# NanoV3_2.net
KiCad netlist of a schematic drawn in EAGLE
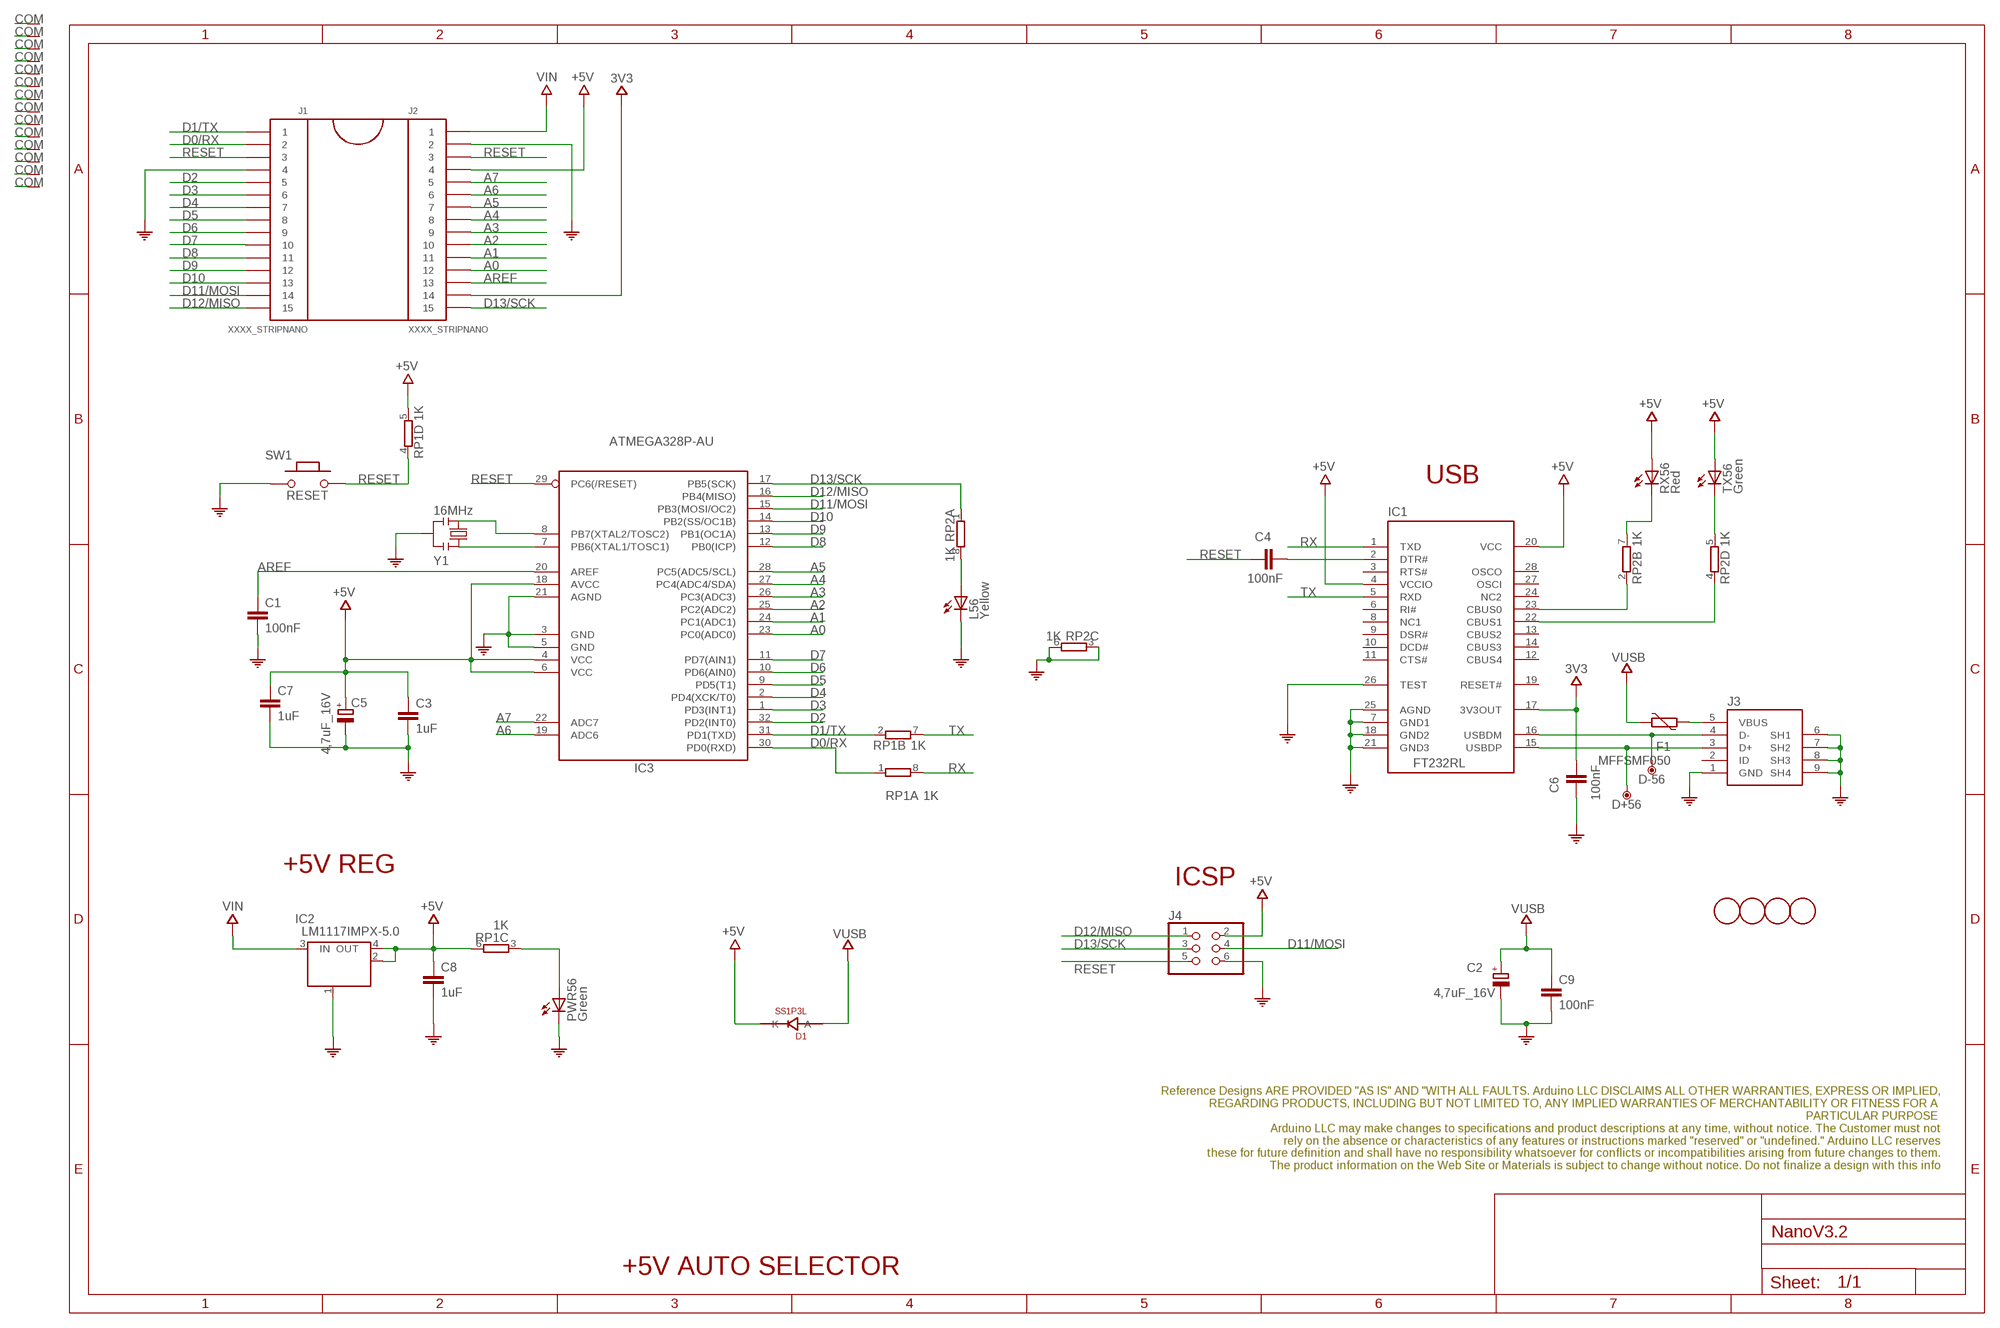
[diagram p0: schematic, sheet 1]

(export (version "E")
  (design (tool "Eeschema 10.0.6"))
  (components
    (comp (ref "C1")
      (value "100nF")
      (footprint "eagle-import:C0603-ROUND")
      (fields (field (name "PART_NUMBER") "cl10b104kbnc"))
      (libsource (lib "eagle-import") (part "0015_100NF_0603"))
    )
    (comp (ref "C2")
      (value "4,7uF_16V")
      (footprint "eagle-import:TAN-A")
      (fields (field (name "PART_NUMBER") "TAJA475MO16RNJ"))
      (libsource (lib "eagle-import") (part "0833_TAJA475MO16RNJ"))
    )
    (comp (ref "C3")
      (value "1uF")
      (footprint "eagle-import:C0603-ROUND")
      (fields (field (name "PART_NUMBER") "1uF_0603/GRM188R61E105KA12D"))
      (libsource (lib "eagle-import") (part "0006_1UF_0603/GRM188R61E105KA12D"))
    )
    (comp (ref "C4")
      (value "100nF")
      (footprint "eagle-import:C0603-ROUND")
      (fields (field (name "PART_NUMBER") "cl10b104kbnc"))
      (libsource (lib "eagle-import") (part "0015_100NF_0603"))
    )
    (comp (ref "C5")
      (value "4,7uF_16V")
      (footprint "eagle-import:TAN-A")
      (fields (field (name "PART_NUMBER") "TAJA475MO16RNJ"))
      (libsource (lib "eagle-import") (part "0833_TAJA475MO16RNJ"))
    )
    (comp (ref "C6")
      (value "100nF")
      (footprint "eagle-import:C0603-ROUND")
      (fields (field (name "PART_NUMBER") "cl10b104kbnc"))
      (libsource (lib "eagle-import") (part "0015_100NF_0603"))
    )
    (comp (ref "C7")
      (value "1uF")
      (footprint "eagle-import:C0603-ROUND")
      (fields (field (name "PART_NUMBER") "1uF_0603/GRM188R61E105KA12D"))
      (libsource (lib "eagle-import") (part "0006_1UF_0603/GRM188R61E105KA12D"))
    )
    (comp (ref "C8")
      (value "1uF")
      (footprint "eagle-import:C0603-ROUND")
      (fields (field (name "PART_NUMBER") "1uF_0603/GRM188R61E105KA12D"))
      (libsource (lib "eagle-import") (part "0006_1UF_0603/GRM188R61E105KA12D"))
    )
    (comp (ref "C9")
      (value "100nF")
      (footprint "eagle-import:C0603-ROUND")
      (fields (field (name "PART_NUMBER") "cl10b104kbnc"))
      (libsource (lib "eagle-import") (part "0015_100NF_0603"))
    )
    (comp (ref "D+56")
      (value "DNP")
      (footprint "eagle-import:TP-1.00MM")
      (libsource (lib "eagle-import") (part "TPTP-1.00MM"))
    )
    (comp (ref "D-56")
      (value "DNP")
      (footprint "eagle-import:TP-1.00MM")
      (libsource (lib "eagle-import") (part "TPTP-1.00MM"))
    )
    (comp (ref "D1")
      (value "SS1P3L")
      (footprint "eagle-import:DO220AAL")
      (fields (field (name "PART_NUMBER") "SS1P3L-M3/84A"))
      (libsource (lib "eagle-import") (part "0025_SS1P3L-M3/84A"))
    )
    (comp (ref "F1")
      (value "MFFSMF050")
      (footprint "eagle-import:0603-1608X90N")
      (fields (field (name "MANUFACTURER") "Bourns Inc "))
      (libsource (lib "eagle-import") (part "PTC"))
    )
    (comp (ref "FRAME1")
      (value "DNP")
      (footprint "eagle-import:FRAME")
      (libsource (lib "eagle-import") (part "A3-FRAME-STANDARD"))
    )
    (comp (ref "IC1")
      (value "FT232RL")
      (footprint "eagle-import:SSOP28")
      (libsource (lib "eagle-import") (part "0226_FT232RL"))
    )
    (comp (ref "IC2")
      (value "LM1117IMPX-5.0")
      (footprint "eagle-import:LINEAR_SOT223")
      (libsource (lib "eagle-import") (part "0022_LM1117IMPX-5.0"))
    )
    (comp (ref "IC3")
      (value "ATMEGA328P-AU")
      (footprint "eagle-import:TQFP32-08")
      (libsource (lib "eagle-import") (part "0265_ATMEGA328P-AU"))
    )
    (comp (ref "J1")
      (value "XXXX_STRIPNANO")
      (footprint "eagle-import:HEAD15-NOSS")
      (libsource (lib "eagle-import") (part "XXXX_STRIPNANO"))
    )
    (comp (ref "J2")
      (value "XXXX_STRIPNANO")
      (footprint "eagle-import:HEAD15-NOSS")
      (libsource (lib "eagle-import") (part "XXXX_STRIPNANO"))
    )
    (comp (ref "J3")
      (value "0219_14850")
      (footprint "eagle-import:USB-MINI-B_2")
      (fields (field (name "PART_NUMBER") "14850"))
      (libsource (lib "eagle-import") (part "0219_14850"))
    )
    (comp (ref "J4")
      (value "0114_PH254-203DF118A00V")
      (footprint "eagle-import:2X03")
      (fields (field (name "PART_NUMBER") "PH254-203DF118A00V"))
      (libsource (lib "eagle-import") (part "0114_PH254-203DF118A00V"))
    )
    (comp (ref "L56")
      (value "Yellow")
      (footprint "eagle-import:CHIPLED_0805")
      (fields (field (name "PART_NUMBER") "KPT-2012YC"))
      (libsource (lib "eagle-import") (part "0044_KPT-2012YC"))
    )
    (comp (ref "PWR56")
      (value "Green")
      (footprint "eagle-import:CHIPLED_0805")
      (fields (field (name "PART_NUMBER") "KPT-2012SGC"))
      (libsource (lib "eagle-import") (part "0043_KPT-2012SGC"))
    )
    (comp (ref "RP1")
      (value "1K")
      (footprint "eagle-import:CAY16")
      (fields (field (name "PART_NUMBER") "064R_1K_/_CAY16-102J4LF"))
      (libsource (lib "eagle-import") (part "0005_064R_1K_/_CAY16-102J4LF"))
    )
    (comp (ref "RP2")
      (value "1K")
      (footprint "eagle-import:CAY16")
      (fields (field (name "PART_NUMBER") "064R_1K_/_CAY16-102J4LF"))
      (libsource (lib "eagle-import") (part "0005_064R_1K_/_CAY16-102J4LF"))
    )
    (comp (ref "RX56")
      (value "Red")
      (footprint "eagle-import:CHIPLED_0805")
      (fields (field (name "PART_NUMBER") "KTP-2012SURCK"))
      (libsource (lib "eagle-import") (part "0181_KTP-2012SURCK"))
    )
    (comp (ref "SW1")
      (value "RESET")
      (footprint "eagle-import:SMD_157SW")
      (fields (field (name "PART_NUMBER") "IT-1185AP1C-160G-G_T&R"))
      (libsource (lib "eagle-import") (part "0173_IT-1185AP1C-160G-G_T&R"))
    )
    (comp (ref "TX56")
      (value "Green")
      (footprint "eagle-import:CHIPLED_0805")
      (fields (field (name "PART_NUMBER") "KPT-2012SGC"))
      (libsource (lib "eagle-import") (part "0043_KPT-2012SGC"))
    )
    (comp (ref "U$4")
      (value "DNP")
      (footprint "eagle-import:FD-1-1.5")
      (libsource (lib "eagle-import") (part "FIDUCIAL-1.5MM"))
    )
    (comp (ref "U$5")
      (value "DNP")
      (footprint "eagle-import:FD-1-1.5")
      (libsource (lib "eagle-import") (part "FIDUCIAL-1.5MM"))
    )
    (comp (ref "U$53")
      (value "DNP")
      (footprint "eagle-import:FD-1-1.5")
      (libsource (lib "eagle-import") (part "FIDUCIAL-1.5MM"))
    )
    (comp (ref "U$54")
      (value "DNP")
      (footprint "eagle-import:FD-1-1.5")
      (libsource (lib "eagle-import") (part "FIDUCIAL-1.5MM"))
    )
    (comp (ref "VP_0")
      (value "VPDEV0")
      (footprint "eagle-import:VPAC0")
      (libsource (lib "eagle-import") (part "VPDEV0"))
    )
    (comp (ref "VP_1")
      (value "VPDEV0")
      (footprint "eagle-import:VPAC0")
      (libsource (lib "eagle-import") (part "VPDEV0"))
    )
    (comp (ref "VP_2")
      (value "VPDEV0")
      (footprint "eagle-import:VPAC0")
      (libsource (lib "eagle-import") (part "VPDEV0"))
    )
    (comp (ref "VP_3")
      (value "VPDEV0")
      (footprint "eagle-import:VPAC0")
      (libsource (lib "eagle-import") (part "VPDEV0"))
    )
    (comp (ref "VP_4")
      (value "VPDEV0")
      (footprint "eagle-import:VPAC0")
      (libsource (lib "eagle-import") (part "VPDEV0"))
    )
    (comp (ref "VP_5")
      (value "VPDEV0")
      (footprint "eagle-import:VPAC0")
      (libsource (lib "eagle-import") (part "VPDEV0"))
    )
    (comp (ref "VP_6")
      (value "VPDEV0")
      (footprint "eagle-import:VPAC0")
      (libsource (lib "eagle-import") (part "VPDEV0"))
    )
    (comp (ref "VP_7")
      (value "VPDEV0")
      (footprint "eagle-import:VPAC0")
      (libsource (lib "eagle-import") (part "VPDEV0"))
    )
    (comp (ref "VP_8")
      (value "VPDEV0")
      (footprint "eagle-import:VPAC0")
      (libsource (lib "eagle-import") (part "VPDEV0"))
    )
    (comp (ref "VP_9")
      (value "VPDEV0")
      (footprint "eagle-import:VPAC0")
      (libsource (lib "eagle-import") (part "VPDEV0"))
    )
    (comp (ref "VP_10")
      (value "VPDEV0")
      (footprint "eagle-import:VPAC0")
      (libsource (lib "eagle-import") (part "VPDEV0"))
    )
    (comp (ref "VP_11")
      (value "VPDEV0")
      (footprint "eagle-import:VPAC0")
      (libsource (lib "eagle-import") (part "VPDEV0"))
    )
    (comp (ref "VP_12")
      (value "VPDEV0")
      (footprint "eagle-import:VPAC0")
      (libsource (lib "eagle-import") (part "VPDEV0"))
    )
    (comp (ref "VP_13")
      (value "VPDEV0")
      (footprint "eagle-import:VPAC0")
      (libsource (lib "eagle-import") (part "VPDEV0"))
    )
    (comp (ref "Y1")
      (value "16MHz")
      (footprint "eagle-import:RESONATOR")
      (fields (field (name "PART_NUMBER") "CSTCE16M0V53-R0"))
      (libsource (lib "eagle-import") (part "0011_CSTCE16M0V53-R0"))
    )
  )
  (nets
    (net (code "1") (name "+5V") (class "Default")
      (node (ref "C3") (pin "1") (pinfunction "1_1") (pintype "passive"))
      (node (ref "C5") (pin "1") (pinfunction "+_1") (pintype "passive"))
      (node (ref "C7") (pin "1") (pinfunction "1_1") (pintype "passive"))
      (node (ref "C8") (pin "1") (pinfunction "1_1") (pintype "passive"))
      (node (ref "D1") (pin "P$1") (pinfunction "K_P$1") (pintype "bidirectional"))
      (node (ref "IC1") (pin "20") (pinfunction "VCC_20") (pintype "power_in"))
      (node (ref "IC1") (pin "4") (pinfunction "VCCIO_4") (pintype "power_in"))
      (node (ref "IC2") (pin "2") (pinfunction "OUT_2") (pintype "passive"))
      (node (ref "IC2") (pin "4") (pinfunction "OUT_4") (pintype "passive"))
      (node (ref "IC3") (pin "18") (pinfunction "AVCC_18") (pintype "bidirectional"))
      (node (ref "IC3") (pin "4") (pinfunction "VCC_4") (pintype "bidirectional"))
      (node (ref "IC3") (pin "6") (pinfunction "VCC_6") (pintype "bidirectional"))
      (node (ref "J2") (pin "4") (pinfunction "4_4") (pintype "passive"))
      (node (ref "J4") (pin "2") (pinfunction "2_2") (pintype "passive"))
      (node (ref "RP1") (pin "5") (pinfunction "2_5") (pintype "passive"))
      (node (ref "RP1") (pin "6") (pinfunction "2_6") (pintype "passive"))
      (node (ref "RX56") (pin "A") (pinfunction "A_A") (pintype "passive"))
      (node (ref "TX56") (pin "A") (pinfunction "A_A") (pintype "passive"))
    )
    (net (code "2") (name "/A0") (class "Default")
      (node (ref "IC3") (pin "23") (pinfunction "PC0(ADC0)_23") (pintype "bidirectional"))
      (node (ref "J2") (pin "12") (pinfunction "12_12") (pintype "passive"))
    )
    (net (code "3") (name "/A1") (class "Default")
      (node (ref "IC3") (pin "24") (pinfunction "PC1(ADC1)_24") (pintype "bidirectional"))
      (node (ref "J2") (pin "11") (pinfunction "11_11") (pintype "passive"))
    )
    (net (code "4") (name "/A2") (class "Default")
      (node (ref "IC3") (pin "25") (pinfunction "PC2(ADC2)_25") (pintype "bidirectional"))
      (node (ref "J2") (pin "10") (pinfunction "10_10") (pintype "passive"))
    )
    (net (code "5") (name "/A3") (class "Default")
      (node (ref "IC3") (pin "26") (pinfunction "PC3(ADC3)_26") (pintype "bidirectional"))
      (node (ref "J2") (pin "9") (pinfunction "9_9") (pintype "passive"))
    )
    (net (code "6") (name "/A4") (class "Default")
      (node (ref "IC3") (pin "27") (pinfunction "PC4(ADC4/SDA)_27") (pintype "bidirectional"))
      (node (ref "J2") (pin "8") (pinfunction "8_8") (pintype "passive"))
    )
    (net (code "7") (name "/A5") (class "Default")
      (node (ref "IC3") (pin "28") (pinfunction "PC5(ADC5/SCL)_28") (pintype "bidirectional"))
      (node (ref "J2") (pin "7") (pinfunction "7_7") (pintype "passive"))
    )
    (net (code "8") (name "/A6") (class "Default")
      (node (ref "IC3") (pin "19") (pinfunction "ADC6_19") (pintype "bidirectional"))
      (node (ref "J2") (pin "6") (pinfunction "6_6") (pintype "passive"))
    )
    (net (code "9") (name "/A7") (class "Default")
      (node (ref "IC3") (pin "22") (pinfunction "ADC7_22") (pintype "bidirectional"))
      (node (ref "J2") (pin "5") (pinfunction "5_5") (pintype "passive"))
    )
    (net (code "10") (name "/AREF") (class "Default")
      (node (ref "C1") (pin "1") (pinfunction "1_1") (pintype "passive"))
      (node (ref "IC3") (pin "20") (pinfunction "AREF_20") (pintype "bidirectional"))
      (node (ref "J2") (pin "13") (pinfunction "13_13") (pintype "passive"))
    )
    (net (code "11") (name "/D0{slash}RX") (class "Default")
      (node (ref "IC3") (pin "30") (pinfunction "PD0(RXD)_30") (pintype "bidirectional"))
      (node (ref "J1") (pin "2") (pinfunction "2_2") (pintype "passive"))
      (node (ref "RP1") (pin "1") (pinfunction "1_1") (pintype "passive"))
    )
    (net (code "12") (name "/D1{slash}TX") (class "Default")
      (node (ref "IC3") (pin "31") (pinfunction "PD1(TXD)_31") (pintype "bidirectional"))
      (node (ref "J1") (pin "1") (pinfunction "1_1") (pintype "passive"))
      (node (ref "RP1") (pin "2") (pinfunction "1_2") (pintype "passive"))
    )
    (net (code "13") (name "/D2") (class "Default")
      (node (ref "IC3") (pin "32") (pinfunction "PD2(INT0)_32") (pintype "bidirectional"))
      (node (ref "J1") (pin "5") (pinfunction "5_5") (pintype "passive"))
    )
    (net (code "14") (name "/D3") (class "Default")
      (node (ref "IC3") (pin "1") (pinfunction "PD3(INT1)_1") (pintype "bidirectional"))
      (node (ref "J1") (pin "6") (pinfunction "6_6") (pintype "passive"))
    )
    (net (code "15") (name "/D4") (class "Default")
      (node (ref "IC3") (pin "2") (pinfunction "PD4(XCK/T0)_2") (pintype "bidirectional"))
      (node (ref "J1") (pin "7") (pinfunction "7_7") (pintype "passive"))
    )
    (net (code "16") (name "/D5") (class "Default")
      (node (ref "IC3") (pin "9") (pinfunction "PD5(T1)_9") (pintype "bidirectional"))
      (node (ref "J1") (pin "8") (pinfunction "8_8") (pintype "passive"))
    )
    (net (code "17") (name "/D6") (class "Default")
      (node (ref "IC3") (pin "10") (pinfunction "PD6(AIN0)_10") (pintype "bidirectional"))
      (node (ref "J1") (pin "9") (pinfunction "9_9") (pintype "passive"))
    )
    (net (code "18") (name "/D7") (class "Default")
      (node (ref "IC3") (pin "11") (pinfunction "PD7(AIN1)_11") (pintype "bidirectional"))
      (node (ref "J1") (pin "10") (pinfunction "10_10") (pintype "passive"))
    )
    (net (code "19") (name "/D8") (class "Default")
      (node (ref "IC3") (pin "12") (pinfunction "PB0(ICP)_12") (pintype "bidirectional"))
      (node (ref "J1") (pin "11") (pinfunction "11_11") (pintype "passive"))
    )
    (net (code "20") (name "/D9") (class "Default")
      (node (ref "IC3") (pin "13") (pinfunction "PB1(OC1A)_13") (pintype "bidirectional"))
      (node (ref "J1") (pin "12") (pinfunction "12_12") (pintype "passive"))
    )
    (net (code "21") (name "/D10") (class "Default")
      (node (ref "IC3") (pin "14") (pinfunction "PB2(SS/OC1B)_14") (pintype "bidirectional"))
      (node (ref "J1") (pin "13") (pinfunction "13_13") (pintype "passive"))
    )
    (net (code "22") (name "/D11{slash}MOSI") (class "Default")
      (node (ref "IC3") (pin "15") (pinfunction "PB3(MOSI/OC2)_15") (pintype "bidirectional"))
      (node (ref "J1") (pin "14") (pinfunction "14_14") (pintype "passive"))
      (node (ref "J4") (pin "4") (pinfunction "4_4") (pintype "passive"))
    )
    (net (code "23") (name "/D12{slash}MISO") (class "Default")
      (node (ref "IC3") (pin "16") (pinfunction "PB4(MISO)_16") (pintype "bidirectional"))
      (node (ref "J1") (pin "15") (pinfunction "15_15") (pintype "passive"))
      (node (ref "J4") (pin "1") (pinfunction "1_1") (pintype "passive"))
    )
    (net (code "24") (name "/D13{slash}SCK") (class "Default")
      (node (ref "IC3") (pin "17") (pinfunction "PB5(SCK)_17") (pintype "bidirectional"))
      (node (ref "J2") (pin "15") (pinfunction "15_15") (pintype "passive"))
      (node (ref "J4") (pin "3") (pinfunction "3_3") (pintype "passive"))
      (node (ref "RP2") (pin "1") (pinfunction "1_1") (pintype "passive"))
    )
    (net (code "25") (name "/RESET") (class "Default")
      (node (ref "C4") (pin "1") (pinfunction "1_1") (pintype "passive"))
      (node (ref "IC3") (pin "29") (pinfunction "PC6(/RESET)_29") (pintype "bidirectional"))
      (node (ref "J1") (pin "3") (pinfunction "3_3") (pintype "passive"))
      (node (ref "J2") (pin "3") (pinfunction "3_3") (pintype "passive"))
      (node (ref "J4") (pin "5") (pinfunction "5_5") (pintype "passive"))
      (node (ref "RP1") (pin "4") (pinfunction "1_4") (pintype "passive"))
      (node (ref "SW1") (pin "2") (pinfunction "2_2") (pintype "passive"))
    )
    (net (code "26") (name "/RX") (class "Default")
      (node (ref "IC1") (pin "1") (pinfunction "TXD_1") (pintype "output"))
      (node (ref "RP1") (pin "8") (pinfunction "2_8") (pintype "passive"))
    )
    (net (code "27") (name "/TX") (class "Default")
      (node (ref "IC1") (pin "5") (pinfunction "RXD_5") (pintype "input"))
      (node (ref "RP1") (pin "7") (pinfunction "2_7") (pintype "passive"))
    )
    (net (code "28") (name "3V3") (class "Default")
      (node (ref "C6") (pin "2") (pinfunction "2_2") (pintype "passive"))
      (node (ref "IC1") (pin "17") (pinfunction "3V3OUT_17") (pintype "power_in"))
      (node (ref "J2") (pin "14") (pinfunction "14_14") (pintype "passive"))
    )
    (net (code "29") (name "COM") (class "Default")
      (node (ref "C1") (pin "2") (pinfunction "2_2") (pintype "passive"))
      (node (ref "C2") (pin "2") (pinfunction "-_2") (pintype "passive"))
      (node (ref "C3") (pin "2") (pinfunction "2_2") (pintype "passive"))
      (node (ref "C5") (pin "2") (pinfunction "-_2") (pintype "passive"))
      (node (ref "C6") (pin "1") (pinfunction "1_1") (pintype "passive"))
      (node (ref "C7") (pin "2") (pinfunction "2_2") (pintype "passive"))
      (node (ref "C8") (pin "2") (pinfunction "2_2") (pintype "passive"))
      (node (ref "C9") (pin "2") (pinfunction "2_2") (pintype "passive"))
      (node (ref "IC1") (pin "18") (pinfunction "GND2_18") (pintype "power_in"))
      (node (ref "IC1") (pin "21") (pinfunction "GND3_21") (pintype "power_in"))
      (node (ref "IC1") (pin "25") (pinfunction "AGND_25") (pintype "power_in"))
      (node (ref "IC1") (pin "26") (pinfunction "TEST_26") (pintype "bidirectional"))
      (node (ref "IC1") (pin "7") (pinfunction "GND1_7") (pintype "power_in"))
      (node (ref "IC2") (pin "1") (pinfunction "GND/ADJ_1") (pintype "input"))
      (node (ref "IC3") (pin "21") (pinfunction "AGND_21") (pintype "bidirectional"))
      (node (ref "IC3") (pin "3") (pinfunction "GND_3") (pintype "bidirectional"))
      (node (ref "IC3") (pin "5") (pinfunction "GND_5") (pintype "bidirectional"))
      (node (ref "J1") (pin "4") (pinfunction "4_4") (pintype "passive"))
      (node (ref "J2") (pin "2") (pinfunction "2_2") (pintype "passive"))
      (node (ref "J3") (pin "1") (pinfunction "GND_1") (pintype "passive"))
      (node (ref "J3") (pin "6") (pinfunction "SH1_6") (pintype "passive"))
      (node (ref "J3") (pin "7") (pinfunction "SH2_7") (pintype "passive"))
      (node (ref "J3") (pin "8") (pinfunction "SH3_8") (pintype "passive"))
      (node (ref "J3") (pin "9") (pinfunction "SH4_9") (pintype "passive"))
      (node (ref "J4") (pin "6") (pinfunction "6_6") (pintype "passive"))
      (node (ref "L56") (pin "C") (pinfunction "C_C") (pintype "passive"))
      (node (ref "PWR56") (pin "C") (pinfunction "C_C") (pintype "passive"))
      (node (ref "RP2") (pin "3") (pinfunction "1_3") (pintype "passive"))
      (node (ref "RP2") (pin "6") (pinfunction "2_6") (pintype "passive"))
      (node (ref "SW1") (pin "1") (pinfunction "1_1") (pintype "passive"))
      (node (ref "VP_0") (pin "VP") (pinfunction "VP_VP") (pintype "passive"))
      (node (ref "VP_1") (pin "VP") (pinfunction "VP_VP") (pintype "passive"))
      (node (ref "VP_10") (pin "VP") (pinfunction "VP_VP") (pintype "passive"))
      (node (ref "VP_11") (pin "VP") (pinfunction "VP_VP") (pintype "passive"))
      (node (ref "VP_12") (pin "VP") (pinfunction "VP_VP") (pintype "passive"))
      (node (ref "VP_13") (pin "VP") (pinfunction "VP_VP") (pintype "passive"))
      (node (ref "VP_2") (pin "VP") (pinfunction "VP_VP") (pintype "passive"))
      (node (ref "VP_3") (pin "VP") (pinfunction "VP_VP") (pintype "passive"))
      (node (ref "VP_4") (pin "VP") (pinfunction "VP_VP") (pintype "passive"))
      (node (ref "VP_5") (pin "VP") (pinfunction "VP_VP") (pintype "passive"))
      (node (ref "VP_6") (pin "VP") (pinfunction "VP_VP") (pintype "passive"))
      (node (ref "VP_7") (pin "VP") (pinfunction "VP_VP") (pintype "passive"))
      (node (ref "VP_8") (pin "VP") (pinfunction "VP_VP") (pintype "passive"))
      (node (ref "VP_9") (pin "VP") (pinfunction "VP_VP") (pintype "passive"))
      (node (ref "Y1") (pin "2") (pinfunction "2_2") (pintype "passive"))
    )
    (net (code "30") (name "Net-(D+56-P$1)") (class "Default")
      (node (ref "D+56") (pin "X") (pinfunction "P$1_X") (pintype "passive"))
      (node (ref "IC1") (pin "15") (pinfunction "USBDP_15") (pintype "bidirectional"))
      (node (ref "J3") (pin "3") (pinfunction "D+_3") (pintype "bidirectional"))
    )
    (net (code "31") (name "Net-(D-56-P$1)") (class "Default")
      (node (ref "D-56") (pin "X") (pinfunction "P$1_X") (pintype "passive"))
      (node (ref "IC1") (pin "16") (pinfunction "USBDM_16") (pintype "bidirectional"))
      (node (ref "J3") (pin "4") (pinfunction "D-_4") (pintype "bidirectional"))
    )
    (net (code "32") (name "Net-(IC1-CBUS0)") (class "Default")
      (node (ref "IC1") (pin "23") (pinfunction "CBUS0_23") (pintype "bidirectional"))
      (node (ref "RP2") (pin "2") (pinfunction "1_2") (pintype "passive"))
    )
    (net (code "33") (name "Net-(IC1-CBUS1)") (class "Default")
      (node (ref "IC1") (pin "22") (pinfunction "CBUS1_22") (pintype "bidirectional"))
      (node (ref "RP2") (pin "4") (pinfunction "1_4") (pintype "passive"))
    )
    (net (code "34") (name "Net-(IC1-DTR#)") (class "Default")
      (node (ref "C4") (pin "2") (pinfunction "2_2") (pintype "passive"))
      (node (ref "IC1") (pin "2") (pinfunction "DTR#_2") (pintype "output"))
    )
    (net (code "35") (name "Net-(IC3-PB6(XTAL1{slash}TOSC1))") (class "Default")
      (node (ref "IC3") (pin "7") (pinfunction "PB6(XTAL1/TOSC1)_7") (pintype "bidirectional"))
      (node (ref "Y1") (pin "1") (pinfunction "1_1") (pintype "passive"))
    )
    (net (code "36") (name "Net-(IC3-PB7(XTAL2{slash}TOSC2))") (class "Default")
      (node (ref "IC3") (pin "8") (pinfunction "PB7(XTAL2/TOSC2)_8") (pintype "bidirectional"))
      (node (ref "Y1") (pin "3") (pinfunction "3_3") (pintype "passive"))
    )
    (net (code "37") (name "Net-(J3-VBUS)") (class "Default")
      (node (ref "F1") (pin "2") (pinfunction "2_2") (pintype "passive"))
      (node (ref "J3") (pin "5") (pinfunction "VBUS_5") (pintype "power_in"))
    )
    (net (code "38") (name "Net-(RP1C-1)") (class "Default")
      (node (ref "PWR56") (pin "A") (pinfunction "A_A") (pintype "passive"))
      (node (ref "RP1") (pin "3") (pinfunction "1_3") (pintype "passive"))
    )
    (net (code "39") (name "Net-(RP2A-2)") (class "Default")
      (node (ref "L56") (pin "A") (pinfunction "A_A") (pintype "passive"))
      (node (ref "RP2") (pin "8") (pinfunction "2_8") (pintype "passive"))
    )
    (net (code "40") (name "Net-(RP2B-2)") (class "Default")
      (node (ref "RP2") (pin "7") (pinfunction "2_7") (pintype "passive"))
      (node (ref "RX56") (pin "C") (pinfunction "C_C") (pintype "passive"))
    )
    (net (code "41") (name "Net-(RP2D-2)") (class "Default")
      (node (ref "RP2") (pin "5") (pinfunction "2_5") (pintype "passive"))
      (node (ref "TX56") (pin "C") (pinfunction "C_C") (pintype "passive"))
    )
    (net (code "42") (name "VIN") (class "Default")
      (node (ref "IC2") (pin "3") (pinfunction "IN_3") (pintype "input"))
      (node (ref "J2") (pin "1") (pinfunction "1_1") (pintype "passive"))
    )
    (net (code "43") (name "VUSB") (class "Default")
      (node (ref "C2") (pin "1") (pinfunction "+_1") (pintype "passive"))
      (node (ref "C9") (pin "1") (pinfunction "1_1") (pintype "passive"))
      (node (ref "D1") (pin "P$2") (pinfunction "A_P$2") (pintype "bidirectional"))
      (node (ref "F1") (pin "1") (pinfunction "1_1") (pintype "passive"))
    )
    (net (code "44") (name "unconnected-(IC1-CBUS2-Pad13)") (class "Default")
      (node (ref "IC1") (pin "13") (pinfunction "CBUS2_13") (pintype "bidirectional"))
    )
    (net (code "45") (name "unconnected-(IC1-CBUS3-Pad14)") (class "Default")
      (node (ref "IC1") (pin "14") (pinfunction "CBUS3_14") (pintype "bidirectional"))
    )
    (net (code "46") (name "unconnected-(IC1-CBUS4-Pad12)") (class "Default")
      (node (ref "IC1") (pin "12") (pinfunction "CBUS4_12") (pintype "bidirectional"))
    )
    (net (code "47") (name "unconnected-(IC1-CTS#-Pad11)") (class "Default")
      (node (ref "IC1") (pin "11") (pinfunction "CTS#_11") (pintype "bidirectional"))
    )
    (net (code "48") (name "unconnected-(IC1-DCD#-Pad10)") (class "Default")
      (node (ref "IC1") (pin "10") (pinfunction "DCD#_10") (pintype "bidirectional"))
    )
    (net (code "49") (name "unconnected-(IC1-DSR#-Pad9)") (class "Default")
      (node (ref "IC1") (pin "9") (pinfunction "DSR#_9") (pintype "bidirectional"))
    )
    (net (code "50") (name "unconnected-(IC1-NC1-Pad8)") (class "Default")
      (node (ref "IC1") (pin "8") (pinfunction "NC1_8") (pintype "bidirectional"))
    )
    (net (code "51") (name "unconnected-(IC1-NC2-Pad24)") (class "Default")
      (node (ref "IC1") (pin "24") (pinfunction "NC2_24") (pintype "no_connect"))
    )
    (net (code "52") (name "unconnected-(IC1-OSCI-Pad27)") (class "Default")
      (node (ref "IC1") (pin "27") (pinfunction "OSCI_27") (pintype "bidirectional"))
    )
    (net (code "53") (name "unconnected-(IC1-OSCO-Pad28)") (class "Default")
      (node (ref "IC1") (pin "28") (pinfunction "OSCO_28") (pintype "output"))
    )
    (net (code "54") (name "unconnected-(IC1-RESET#-Pad19)") (class "Default")
      (node (ref "IC1") (pin "19") (pinfunction "RESET#_19") (pintype "bidirectional"))
    )
    (net (code "55") (name "unconnected-(IC1-RI#-Pad6)") (class "Default")
      (node (ref "IC1") (pin "6") (pinfunction "RI#_6") (pintype "bidirectional"))
    )
    (net (code "56") (name "unconnected-(IC1-RTS#-Pad3)") (class "Default")
      (node (ref "IC1") (pin "3") (pinfunction "RTS#_3") (pintype "output"))
    )
    (net (code "57") (name "unconnected-(J3-ID-Pad2)") (class "Default")
      (node (ref "J3") (pin "2") (pinfunction "ID_2") (pintype "bidirectional"))
    )
  )
)
